# otterley_A_v1_1.net
KiCad netlist of a schematic drawn in EAGLE
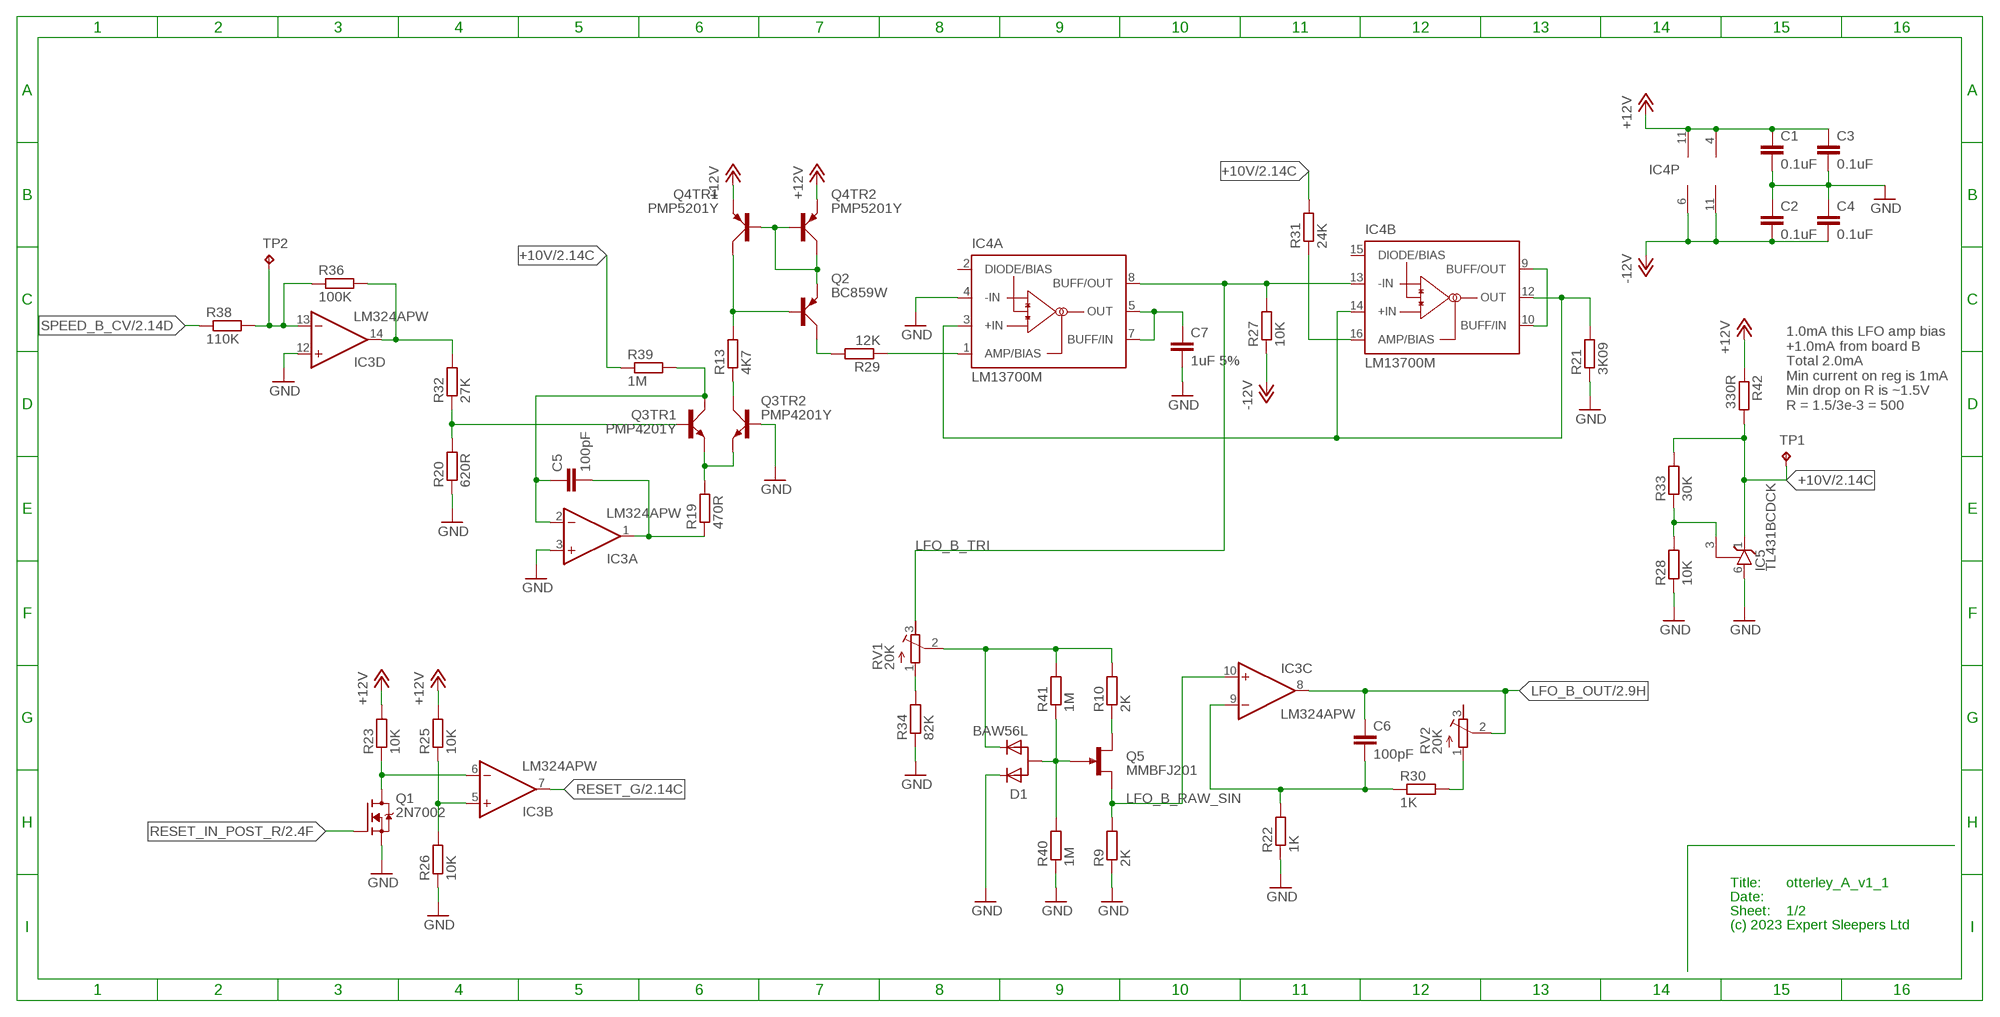
[diagram p0: schematic, sheet 1]
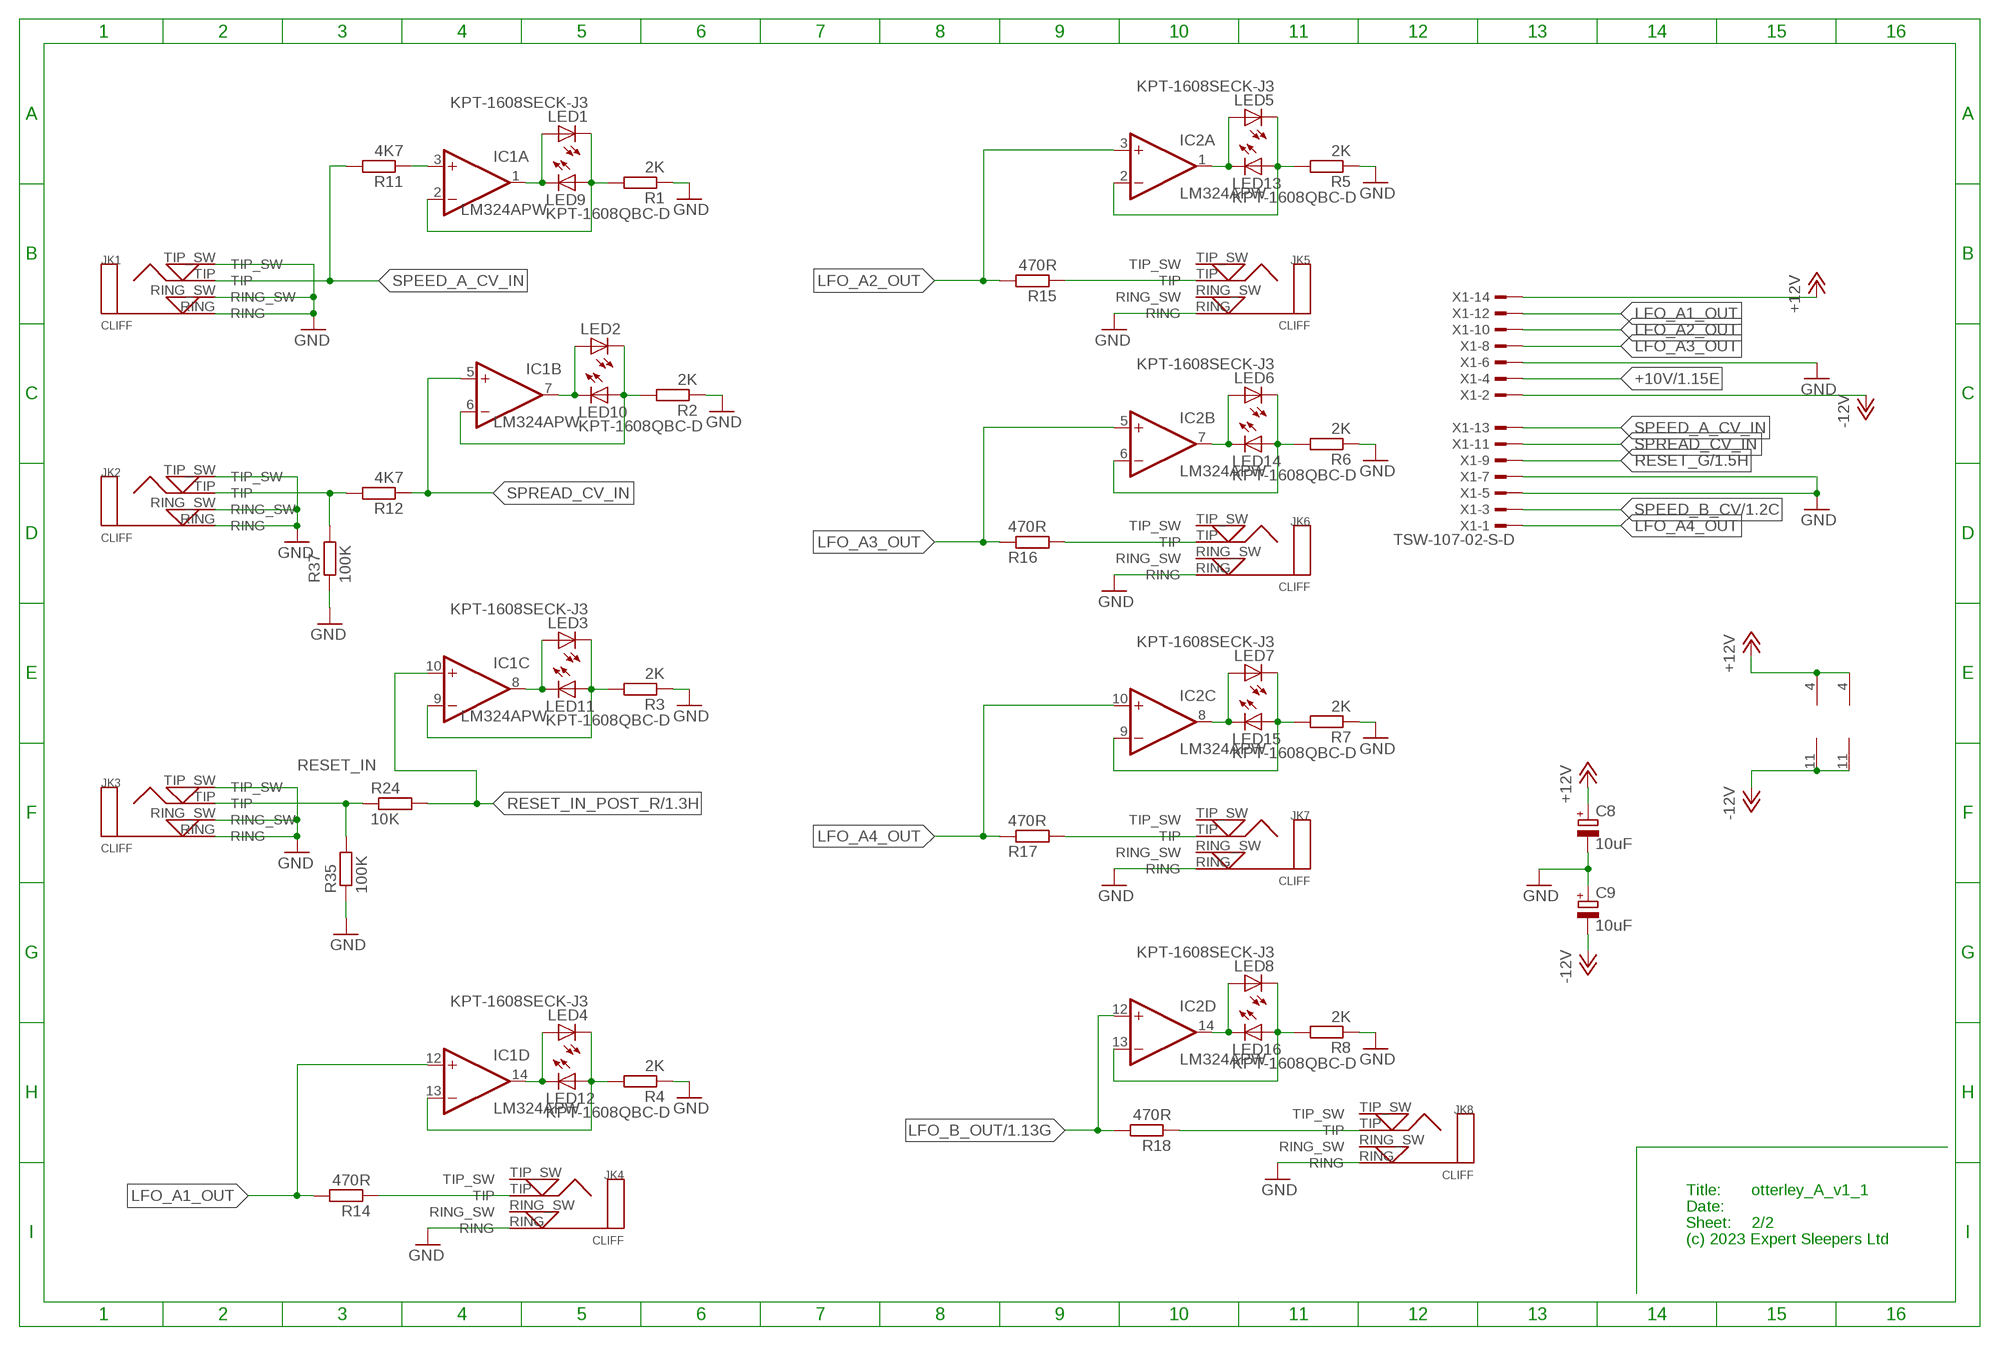
[diagram p1: schematic, sheet 2]

(export (version "E")
  (design (tool "Eeschema 10.0.6"))
  (components
    (comp (ref "C8")
      (value "10uF")
      (footprint "eagle-import:UD-4X5,8_NICHICON")
      (libsource (lib "eagle-import") (part "CPOL-EUUD-4X5,8"))
    )
    (comp (ref "C9")
      (value "10uF")
      (footprint "eagle-import:UD-4X5,8_NICHICON")
      (libsource (lib "eagle-import") (part "CPOL-EUUD-4X5,8"))
    )
    (comp (ref "IC1")
      (value "LM324APW")
      (footprint "eagle-import:PW_R-PDSO-G14")
      (libsource (lib "eagle-import") (part "TL074PW"))
    )
    (comp (ref "IC2")
      (value "LM324APW")
      (footprint "eagle-import:PW_R-PDSO-G14")
      (libsource (lib "eagle-import") (part "TL074PW"))
    )
    (comp (ref "JK1")
      (value "CLIFF")
      (footprint "eagle-import:CLIFF3.5MMPCB")
      (libsource (lib "eagle-import") (part "CLIFF3.5MM_PCB_SW_JK"))
    )
    (comp (ref "JK2")
      (value "CLIFF")
      (footprint "eagle-import:CLIFF3.5MMPCB")
      (libsource (lib "eagle-import") (part "CLIFF3.5MM_PCB_SW_JK"))
    )
    (comp (ref "JK3")
      (value "CLIFF")
      (footprint "eagle-import:CLIFF3.5MMPCB")
      (libsource (lib "eagle-import") (part "CLIFF3.5MM_PCB_SW_JK"))
    )
    (comp (ref "JK4")
      (value "CLIFF")
      (footprint "eagle-import:CLIFF3.5MMPCB")
      (libsource (lib "eagle-import") (part "CLIFF3.5MM_PCB_SW_JK"))
    )
    (comp (ref "JK5")
      (value "CLIFF")
      (footprint "eagle-import:CLIFF3.5MMPCB")
      (libsource (lib "eagle-import") (part "CLIFF3.5MM_PCB_SW_JK"))
    )
    (comp (ref "JK6")
      (value "CLIFF")
      (footprint "eagle-import:CLIFF3.5MMPCB")
      (libsource (lib "eagle-import") (part "CLIFF3.5MM_PCB_SW_JK"))
    )
    (comp (ref "JK7")
      (value "CLIFF")
      (footprint "eagle-import:CLIFF3.5MMPCB")
      (libsource (lib "eagle-import") (part "CLIFF3.5MM_PCB_SW_JK"))
    )
    (comp (ref "JK8")
      (value "CLIFF")
      (footprint "eagle-import:CLIFF3.5MMPCB")
      (libsource (lib "eagle-import") (part "CLIFF3.5MM_PCB_SW_JK"))
    )
    (comp (ref "LED1")
      (value "KPT-1608SECK-J3")
      (footprint "eagle-import:CHIPLED_0603_LEFT")
      (libsource (lib "eagle-import") (part "KPT-1608SECK-J3"))
    )
    (comp (ref "LED2")
      (value "KPT-1608SECK-J3")
      (footprint "eagle-import:CHIPLED_0603_LEFT")
      (libsource (lib "eagle-import") (part "KPT-1608SECK-J3"))
    )
    (comp (ref "LED3")
      (value "KPT-1608SECK-J3")
      (footprint "eagle-import:CHIPLED_0603_LEFT")
      (libsource (lib "eagle-import") (part "KPT-1608SECK-J3"))
    )
    (comp (ref "LED4")
      (value "KPT-1608SECK-J3")
      (footprint "eagle-import:CHIPLED_0603_LEFT")
      (libsource (lib "eagle-import") (part "KPT-1608SECK-J3"))
    )
    (comp (ref "LED5")
      (value "KPT-1608SECK-J3")
      (footprint "eagle-import:CHIPLED_0603_LEFT")
      (libsource (lib "eagle-import") (part "KPT-1608SECK-J3"))
    )
    (comp (ref "LED6")
      (value "KPT-1608SECK-J3")
      (footprint "eagle-import:CHIPLED_0603_LEFT")
      (libsource (lib "eagle-import") (part "KPT-1608SECK-J3"))
    )
    (comp (ref "LED7")
      (value "KPT-1608SECK-J3")
      (footprint "eagle-import:CHIPLED_0603_LEFT")
      (libsource (lib "eagle-import") (part "KPT-1608SECK-J3"))
    )
    (comp (ref "LED8")
      (value "KPT-1608SECK-J3")
      (footprint "eagle-import:CHIPLED_0603_LEFT")
      (libsource (lib "eagle-import") (part "KPT-1608SECK-J3"))
    )
    (comp (ref "LED9")
      (value "KPT-1608QBC-D")
      (footprint "eagle-import:CHIPLED_0603_RIGHT")
      (libsource (lib "eagle-import") (part "KPT-1608QBC-D"))
    )
    (comp (ref "LED10")
      (value "KPT-1608QBC-D")
      (footprint "eagle-import:CHIPLED_0603_RIGHT")
      (libsource (lib "eagle-import") (part "KPT-1608QBC-D"))
    )
    (comp (ref "LED11")
      (value "KPT-1608QBC-D")
      (footprint "eagle-import:CHIPLED_0603_RIGHT")
      (libsource (lib "eagle-import") (part "KPT-1608QBC-D"))
    )
    (comp (ref "LED12")
      (value "KPT-1608QBC-D")
      (footprint "eagle-import:CHIPLED_0603_RIGHT")
      (libsource (lib "eagle-import") (part "KPT-1608QBC-D"))
    )
    (comp (ref "LED13")
      (value "KPT-1608QBC-D")
      (footprint "eagle-import:CHIPLED_0603_RIGHT")
      (libsource (lib "eagle-import") (part "KPT-1608QBC-D"))
    )
    (comp (ref "LED14")
      (value "KPT-1608QBC-D")
      (footprint "eagle-import:CHIPLED_0603_RIGHT")
      (libsource (lib "eagle-import") (part "KPT-1608QBC-D"))
    )
    (comp (ref "LED15")
      (value "KPT-1608QBC-D")
      (footprint "eagle-import:CHIPLED_0603_RIGHT")
      (libsource (lib "eagle-import") (part "KPT-1608QBC-D"))
    )
    (comp (ref "LED16")
      (value "KPT-1608QBC-D")
      (footprint "eagle-import:CHIPLED_0603_RIGHT")
      (libsource (lib "eagle-import") (part "KPT-1608QBC-D"))
    )
    (comp (ref "R1")
      (value "2K")
      (footprint "eagle-import:R1206")
      (libsource (lib "eagle-import") (part "R-EU_R1206"))
    )
    (comp (ref "R2")
      (value "2K")
      (footprint "eagle-import:R1206")
      (libsource (lib "eagle-import") (part "R-EU_R1206"))
    )
    (comp (ref "R3")
      (value "2K")
      (footprint "eagle-import:R1206")
      (libsource (lib "eagle-import") (part "R-EU_R1206"))
    )
    (comp (ref "R4")
      (value "2K")
      (footprint "eagle-import:R1206")
      (libsource (lib "eagle-import") (part "R-EU_R1206"))
    )
    (comp (ref "R5")
      (value "2K")
      (footprint "eagle-import:R1206")
      (libsource (lib "eagle-import") (part "R-EU_R1206"))
    )
    (comp (ref "R6")
      (value "2K")
      (footprint "eagle-import:R1206")
      (libsource (lib "eagle-import") (part "R-EU_R1206"))
    )
    (comp (ref "R7")
      (value "2K")
      (footprint "eagle-import:R1206")
      (libsource (lib "eagle-import") (part "R-EU_R1206"))
    )
    (comp (ref "R8")
      (value "2K")
      (footprint "eagle-import:R1206")
      (libsource (lib "eagle-import") (part "R-EU_R1206"))
    )
    (comp (ref "R11")
      (value "4K7")
      (footprint "eagle-import:R1206")
      (libsource (lib "eagle-import") (part "R-EU_R1206"))
    )
    (comp (ref "R12")
      (value "4K7")
      (footprint "eagle-import:R1206")
      (libsource (lib "eagle-import") (part "R-EU_R1206"))
    )
    (comp (ref "R14")
      (value "470R")
      (footprint "eagle-import:R1206")
      (libsource (lib "eagle-import") (part "R-EU_R1206"))
    )
    (comp (ref "R15")
      (value "470R")
      (footprint "eagle-import:R1206")
      (libsource (lib "eagle-import") (part "R-EU_R1206"))
    )
    (comp (ref "R16")
      (value "470R")
      (footprint "eagle-import:R1206")
      (libsource (lib "eagle-import") (part "R-EU_R1206"))
    )
    (comp (ref "R17")
      (value "470R")
      (footprint "eagle-import:R1206")
      (libsource (lib "eagle-import") (part "R-EU_R1206"))
    )
    (comp (ref "R18")
      (value "470R")
      (footprint "eagle-import:R1206")
      (libsource (lib "eagle-import") (part "R-EU_R1206"))
    )
    (comp (ref "R24")
      (value "10K")
      (footprint "eagle-import:R0603")
      (libsource (lib "eagle-import") (part "R-EU_R0603"))
    )
    (comp (ref "R35")
      (value "100K")
      (footprint "eagle-import:R0603")
      (libsource (lib "eagle-import") (part "R-EU_R0603"))
    )
    (comp (ref "R37")
      (value "100K")
      (footprint "eagle-import:R0603")
      (libsource (lib "eagle-import") (part "R-EU_R0603"))
    )
    (comp (ref "X1")
      (value "TSW-107-02-S-D")
      (footprint "eagle-import:TSW-107-02-S-D")
      (libsource (lib "eagle-import") (part "TSW-107-02-S-D"))
    )
    (comp (ref "C1")
      (value "0.1uF")
      (footprint "eagle-import:C0402")
      (libsource (lib "eagle-import") (part "C-EUC0402"))
    )
    (comp (ref "C2")
      (value "0.1uF")
      (footprint "eagle-import:C0402")
      (libsource (lib "eagle-import") (part "C-EUC0402"))
    )
    (comp (ref "C3")
      (value "0.1uF")
      (footprint "eagle-import:C0402")
      (libsource (lib "eagle-import") (part "C-EUC0402"))
    )
    (comp (ref "C4")
      (value "0.1uF")
      (footprint "eagle-import:C0402")
      (libsource (lib "eagle-import") (part "C-EUC0402"))
    )
    (comp (ref "C5")
      (value "100pF")
      (footprint "eagle-import:C0603")
      (libsource (lib "eagle-import") (part "C-EUC0603"))
    )
    (comp (ref "C6")
      (value "100pF")
      (footprint "eagle-import:C0603")
      (libsource (lib "eagle-import") (part "C-EUC0603"))
    )
    (comp (ref "C7")
      (value "1uF 5%")
      (footprint "eagle-import:C0805")
      (libsource (lib "eagle-import") (part "C-EUC0805"))
    )
    (comp (ref "D1")
      (value "BAW56L")
      (footprint "eagle-import:SOT-23")
      (libsource (lib "eagle-import") (part "BAW56L"))
    )
    (comp (ref "IC3")
      (value "LM324APW")
      (footprint "eagle-import:PW_R-PDSO-G14")
      (libsource (lib "eagle-import") (part "TL074PW"))
    )
    (comp (ref "IC4")
      (value "LM13700M")
      (footprint "eagle-import:SO16")
      (libsource (lib "eagle-import") (part "LM13700M"))
    )
    (comp (ref "IC5")
      (value "TL431BCDCK")
      (footprint "eagle-import:DCK_SC-70")
      (libsource (lib "eagle-import") (part "TL431DCKBC"))
    )
    (comp (ref "Q1")
      (value "2N7002")
      (footprint "eagle-import:SOT23")
      (libsource (lib "eagle-import") (part "2N7002"))
    )
    (comp (ref "Q2")
      (value "BC859W")
      (footprint "eagle-import:SOT323")
      (libsource (lib "eagle-import") (part "BC859W"))
    )
    (comp (ref "Q3")
      (value "PMP4201Y")
      (footprint "eagle-import:SOT65P210X110-6N")
      (fields
        (field (name "ARROW_PART_NUMBER") "PMP4201Y,135")
        (field (name "MOUSER_PART_NUMBER") "771-PMP4201Y135")
      )
      (libsource (lib "eagle-import") (part "PMP4201Y"))
    )
    (comp (ref "Q4")
      (value "PMP5201Y")
      (footprint "eagle-import:SOT65P210X110-6N")
      (fields
        (field (name "ARROW_PART_NUMBER") "PMP5201Y,135")
        (field (name "MOUSER_PART_NUMBER") "771-PMP5201Y135")
      )
      (libsource (lib "eagle-import") (part "PMP5201Y"))
    )
    (comp (ref "Q5")
      (value "MMBFJ201")
      (footprint "eagle-import:SOT23")
      (libsource (lib "eagle-import") (part "MMBFJ3"))
    )
    (comp (ref "R9")
      (value "2K")
      (footprint "eagle-import:R1206")
      (libsource (lib "eagle-import") (part "R-EU_R1206"))
    )
    (comp (ref "R10")
      (value "2K")
      (footprint "eagle-import:R1206")
      (libsource (lib "eagle-import") (part "R-EU_R1206"))
    )
    (comp (ref "R13")
      (value "4K7")
      (footprint "eagle-import:R1206")
      (libsource (lib "eagle-import") (part "R-EU_R1206"))
    )
    (comp (ref "R19")
      (value "470R")
      (footprint "eagle-import:R1206")
      (libsource (lib "eagle-import") (part "R-EU_R1206"))
    )
    (comp (ref "R20")
      (value "620R")
      (footprint "eagle-import:R0603")
      (libsource (lib "eagle-import") (part "R-EU_R0603"))
    )
    (comp (ref "R21")
      (value "3K09")
      (footprint "eagle-import:R0603")
      (libsource (lib "eagle-import") (part "R-EU_R0603"))
    )
    (comp (ref "R22")
      (value "1K")
      (footprint "eagle-import:R0603")
      (libsource (lib "eagle-import") (part "R-EU_R0603"))
    )
    (comp (ref "R23")
      (value "10K")
      (footprint "eagle-import:R0603")
      (libsource (lib "eagle-import") (part "R-EU_R0603"))
    )
    (comp (ref "R25")
      (value "10K")
      (footprint "eagle-import:R0603")
      (libsource (lib "eagle-import") (part "R-EU_R0603"))
    )
    (comp (ref "R26")
      (value "10K")
      (footprint "eagle-import:R0603")
      (libsource (lib "eagle-import") (part "R-EU_R0603"))
    )
    (comp (ref "R27")
      (value "10K")
      (footprint "eagle-import:R0603")
      (libsource (lib "eagle-import") (part "R-EU_R0603"))
    )
    (comp (ref "R28")
      (value "10K")
      (footprint "eagle-import:R0603")
      (libsource (lib "eagle-import") (part "R-EU_R0603"))
    )
    (comp (ref "R29")
      (value "12K")
      (footprint "eagle-import:R0603")
      (libsource (lib "eagle-import") (part "R-EU_R0603"))
    )
    (comp (ref "R30")
      (value "1K")
      (footprint "eagle-import:R0603")
      (libsource (lib "eagle-import") (part "R-EU_R0603"))
    )
    (comp (ref "R31")
      (value "24K")
      (footprint "eagle-import:R0603")
      (libsource (lib "eagle-import") (part "R-EU_R0603"))
    )
    (comp (ref "R32")
      (value "27K")
      (footprint "eagle-import:R0603")
      (libsource (lib "eagle-import") (part "R-EU_R0603"))
    )
    (comp (ref "R33")
      (value "30K")
      (footprint "eagle-import:R0603")
      (libsource (lib "eagle-import") (part "R-EU_R0603"))
    )
    (comp (ref "R34")
      (value "82K")
      (footprint "eagle-import:R0603")
      (libsource (lib "eagle-import") (part "R-EU_R0603"))
    )
    (comp (ref "R36")
      (value "100K")
      (footprint "eagle-import:R0603")
      (libsource (lib "eagle-import") (part "R-EU_R0603"))
    )
    (comp (ref "R38")
      (value "110K")
      (footprint "eagle-import:R0603")
      (libsource (lib "eagle-import") (part "R-EU_R0603"))
    )
    (comp (ref "R39")
      (value "1M")
      (footprint "eagle-import:R0603")
      (libsource (lib "eagle-import") (part "R-EU_R0603"))
    )
    (comp (ref "R40")
      (value "1M")
      (footprint "eagle-import:R0603")
      (libsource (lib "eagle-import") (part "R-EU_R0603"))
    )
    (comp (ref "R41")
      (value "1M")
      (footprint "eagle-import:R0603")
      (libsource (lib "eagle-import") (part "R-EU_R0603"))
    )
    (comp (ref "R42")
      (value "330R")
      (footprint "eagle-import:R1206")
      (libsource (lib "eagle-import") (part "R-EU_R1206"))
    )
    (comp (ref "RV1")
      (value "20K")
      (footprint "eagle-import:3306_W")
      (libsource (lib "eagle-import") (part "3306W"))
    )
    (comp (ref "RV2")
      (value "20K")
      (footprint "eagle-import:3306_W")
      (libsource (lib "eagle-import") (part "3306W"))
    )
    (comp (ref "TP1")
      (value "RA2")
      (footprint "eagle-import:P1-13")
      (libsource (lib "eagle-import") (part "TPPAD1-13"))
    )
    (comp (ref "TP2")
      (value "RA2")
      (footprint "eagle-import:P1-13")
      (libsource (lib "eagle-import") (part "TPPAD1-13"))
    )
  )
  (nets
    (net (code "1") (name "+10V") (class "Default")
      (node (ref "IC5") (pin "1") (pinfunction "C_1") (pintype "passive"))
      (node (ref "R31") (pin "2") (pinfunction "2_2") (pintype "passive"))
      (node (ref "R33") (pin "2") (pinfunction "2_2") (pintype "passive"))
      (node (ref "R39") (pin "1") (pinfunction "1_1") (pintype "passive"))
      (node (ref "R42") (pin "2") (pinfunction "2_2") (pintype "passive"))
      (node (ref "TP1") (pin "TP") (pinfunction "TP_TP") (pintype "input"))
      (node (ref "X1") (pin "4") (pinfunction "1_4") (pintype "passive"))
    )
    (net (code "2") (name "+12V") (class "Default")
      (node (ref "C1") (pin "1") (pinfunction "1_1") (pintype "passive"))
      (node (ref "C3") (pin "1") (pinfunction "1_1") (pintype "passive"))
      (node (ref "C8") (pin "+") (pinfunction "+_+") (pintype "passive"))
      (node (ref "IC1") (pin "4") (pinfunction "V+_4") (pintype "power_in"))
      (node (ref "IC2") (pin "4") (pinfunction "V+_4") (pintype "power_in"))
      (node (ref "IC3") (pin "4") (pinfunction "V+_4") (pintype "power_in"))
      (node (ref "IC4") (pin "11") (pinfunction "V+_11") (pintype "power_in"))
      (node (ref "Q4") (pin "4") (pinfunction "E_4") (pintype "passive"))
      (node (ref "Q4") (pin "5") (pinfunction "E_5") (pintype "passive"))
      (node (ref "R23") (pin "2") (pinfunction "2_2") (pintype "passive"))
      (node (ref "R25") (pin "2") (pinfunction "2_2") (pintype "passive"))
      (node (ref "R42") (pin "1") (pinfunction "1_1") (pintype "passive"))
      (node (ref "X1") (pin "14") (pinfunction "1_14") (pintype "passive"))
    )
    (net (code "3") (name "-12V") (class "Default")
      (node (ref "C2") (pin "2") (pinfunction "2_2") (pintype "passive"))
      (node (ref "C4") (pin "2") (pinfunction "2_2") (pintype "passive"))
      (node (ref "C9") (pin "-") (pinfunction "-_-") (pintype "passive"))
      (node (ref "IC1") (pin "11") (pinfunction "V-_11") (pintype "power_in"))
      (node (ref "IC2") (pin "11") (pinfunction "V-_11") (pintype "power_in"))
      (node (ref "IC3") (pin "11") (pinfunction "V-_11") (pintype "power_in"))
      (node (ref "IC4") (pin "6") (pinfunction "V-_6") (pintype "power_in"))
      (node (ref "R27") (pin "1") (pinfunction "1_1") (pintype "passive"))
      (node (ref "X1") (pin "2") (pinfunction "1_2") (pintype "passive"))
    )
    (net (code "4") (name "GND") (class "Default")
      (node (ref "C1") (pin "2") (pinfunction "2_2") (pintype "passive"))
      (node (ref "C2") (pin "1") (pinfunction "1_1") (pintype "passive"))
      (node (ref "C3") (pin "2") (pinfunction "2_2") (pintype "passive"))
      (node (ref "C4") (pin "1") (pinfunction "1_1") (pintype "passive"))
      (node (ref "C7") (pin "2") (pinfunction "2_2") (pintype "passive"))
      (node (ref "C8") (pin "-") (pinfunction "-_-") (pintype "passive"))
      (node (ref "C9") (pin "+") (pinfunction "+_+") (pintype "passive"))
      (node (ref "D1") (pin "1") (pinfunction "C1_1") (pintype "passive"))
      (node (ref "IC3") (pin "12") (pinfunction "+IN_12") (pintype "input"))
      (node (ref "IC3") (pin "3") (pinfunction "+IN_3") (pintype "input"))
      (node (ref "IC4") (pin "4") (pinfunction "-IN_4") (pintype "input"))
      (node (ref "IC5") (pin "6") (pinfunction "A_6") (pintype "passive"))
      (node (ref "JK1") (pin "RING") (pinfunction "RING_RING") (pintype "bidirectional"))
      (node (ref "JK1") (pin "RING_SW") (pinfunction "RING_SW_RING_SW") (pintype "bidirectional"))
      (node (ref "JK1") (pin "TIP_SW") (pinfunction "TIP_SW_TIP_SW") (pintype "bidirectional"))
      (node (ref "JK2") (pin "RING") (pinfunction "RING_RING") (pintype "bidirectional"))
      (node (ref "JK2") (pin "RING_SW") (pinfunction "RING_SW_RING_SW") (pintype "bidirectional"))
      (node (ref "JK2") (pin "TIP_SW") (pinfunction "TIP_SW_TIP_SW") (pintype "bidirectional"))
      (node (ref "JK3") (pin "RING") (pinfunction "RING_RING") (pintype "bidirectional"))
      (node (ref "JK3") (pin "RING_SW") (pinfunction "RING_SW_RING_SW") (pintype "bidirectional"))
      (node (ref "JK3") (pin "TIP_SW") (pinfunction "TIP_SW_TIP_SW") (pintype "bidirectional"))
      (node (ref "JK4") (pin "RING") (pinfunction "RING_RING") (pintype "bidirectional"))
      (node (ref "JK5") (pin "RING") (pinfunction "RING_RING") (pintype "bidirectional"))
      (node (ref "JK6") (pin "RING") (pinfunction "RING_RING") (pintype "bidirectional"))
      (node (ref "JK7") (pin "RING") (pinfunction "RING_RING") (pintype "bidirectional"))
      (node (ref "JK8") (pin "RING") (pinfunction "RING_RING") (pintype "bidirectional"))
      (node (ref "Q1") (pin "2") (pinfunction "S_2") (pintype "passive"))
      (node (ref "Q3") (pin "2") (pinfunction "B_2") (pintype "passive"))
      (node (ref "R1") (pin "1") (pinfunction "1_1") (pintype "passive"))
      (node (ref "R2") (pin "1") (pinfunction "1_1") (pintype "passive"))
      (node (ref "R20") (pin "1") (pinfunction "1_1") (pintype "passive"))
      (node (ref "R21") (pin "1") (pinfunction "1_1") (pintype "passive"))
      (node (ref "R22") (pin "1") (pinfunction "1_1") (pintype "passive"))
      (node (ref "R26") (pin "1") (pinfunction "1_1") (pintype "passive"))
      (node (ref "R28") (pin "1") (pinfunction "1_1") (pintype "passive"))
      (node (ref "R3") (pin "1") (pinfunction "1_1") (pintype "passive"))
      (node (ref "R34") (pin "1") (pinfunction "1_1") (pintype "passive"))
      (node (ref "R35") (pin "1") (pinfunction "1_1") (pintype "passive"))
      (node (ref "R37") (pin "1") (pinfunction "1_1") (pintype "passive"))
      (node (ref "R4") (pin "1") (pinfunction "1_1") (pintype "passive"))
      (node (ref "R40") (pin "1") (pinfunction "1_1") (pintype "passive"))
      (node (ref "R5") (pin "1") (pinfunction "1_1") (pintype "passive"))
      (node (ref "R6") (pin "1") (pinfunction "1_1") (pintype "passive"))
      (node (ref "R7") (pin "1") (pinfunction "1_1") (pintype "passive"))
      (node (ref "R8") (pin "1") (pinfunction "1_1") (pintype "passive"))
      (node (ref "R9") (pin "1") (pinfunction "1_1") (pintype "passive"))
      (node (ref "X1") (pin "5") (pinfunction "1_5") (pintype "passive"))
      (node (ref "X1") (pin "6") (pinfunction "1_6") (pintype "passive"))
      (node (ref "X1") (pin "7") (pinfunction "1_7") (pintype "passive"))
    )
    (net (code "5") (name "LFO_A1_OUT") (class "Default")
      (node (ref "IC1") (pin "12") (pinfunction "+IN_12") (pintype "input"))
      (node (ref "R14") (pin "2") (pinfunction "2_2") (pintype "passive"))
      (node (ref "X1") (pin "12") (pinfunction "1_12") (pintype "passive"))
    )
    (net (code "6") (name "LFO_A2_OUT") (class "Default")
      (node (ref "IC2") (pin "3") (pinfunction "+IN_3") (pintype "input"))
      (node (ref "R15") (pin "2") (pinfunction "2_2") (pintype "passive"))
      (node (ref "X1") (pin "10") (pinfunction "1_10") (pintype "passive"))
    )
    (net (code "7") (name "LFO_A3_OUT") (class "Default")
      (node (ref "IC2") (pin "5") (pinfunction "+IN_5") (pintype "input"))
      (node (ref "R16") (pin "1") (pinfunction "1_1") (pintype "passive"))
      (node (ref "X1") (pin "8") (pinfunction "1_8") (pintype "passive"))
    )
    (net (code "8") (name "LFO_A4_OUT") (class "Default")
      (node (ref "IC2") (pin "10") (pinfunction "+IN_10") (pintype "input"))
      (node (ref "R17") (pin "1") (pinfunction "1_1") (pintype "passive"))
      (node (ref "X1") (pin "1") (pinfunction "1_1") (pintype "passive"))
    )
    (net (code "9") (name "LFO_B_OUT") (class "Default")
      (node (ref "C6") (pin "1") (pinfunction "1_1") (pintype "passive"))
      (node (ref "IC2") (pin "12") (pinfunction "+IN_12") (pintype "input"))
      (node (ref "IC3") (pin "8") (pinfunction "OUT_8") (pintype "output"))
      (node (ref "R18") (pin "2") (pinfunction "2_2") (pintype "passive"))
      (node (ref "RV2") (pin "2") (pinfunction "S_2") (pintype "passive"))
    )
    (net (code "10") (name "LFO_B_RAW_SIN") (class "Default")
      (node (ref "IC3") (pin "10") (pinfunction "+IN_10") (pintype "input"))
      (node (ref "Q5") (pin "2") (pinfunction "S_2") (pintype "passive"))
      (node (ref "R9") (pin "2") (pinfunction "2_2") (pintype "passive"))
    )
    (net (code "11") (name "LFO_B_TRI") (class "Default")
      (node (ref "IC4") (pin "13") (pinfunction "-IN_13") (pintype "input"))
      (node (ref "IC4") (pin "8") (pinfunction "BUFF/OUT_8") (pintype "output"))
      (node (ref "R27") (pin "2") (pinfunction "2_2") (pintype "passive"))
      (node (ref "RV1") (pin "3") (pinfunction "E_3") (pintype "passive"))
    )
    (net (code "12") (name "Net-(D1-A)") (class "Default")
      (node (ref "D1") (pin "3") (pinfunction "A_3") (pintype "passive"))
      (node (ref "Q5") (pin "3") (pinfunction "G_3") (pintype "passive"))
      (node (ref "R40") (pin "2") (pinfunction "2_2") (pintype "passive"))
      (node (ref "R41") (pin "1") (pinfunction "1_1") (pintype "passive"))
    )
    (net (code "13") (name "Net-(D1-C2)") (class "Default")
      (node (ref "D1") (pin "2") (pinfunction "C2_2") (pintype "passive"))
      (node (ref "R10") (pin "2") (pinfunction "2_2") (pintype "passive"))
      (node (ref "R41") (pin "2") (pinfunction "2_2") (pintype "passive"))
      (node (ref "RV1") (pin "2") (pinfunction "S_2") (pintype "passive"))
    )
    (net (code "14") (name "Net-(IC1A-+IN)") (class "Default")
      (node (ref "IC1") (pin "3") (pinfunction "+IN_3") (pintype "input"))
      (node (ref "R11") (pin "1") (pinfunction "1_1") (pintype "passive"))
    )
    (net (code "15") (name "Net-(IC1A--IN)") (class "Default")
      (node (ref "IC1") (pin "2") (pinfunction "-IN_2") (pintype "input"))
      (node (ref "LED1") (pin "1") (pinfunction "C_1") (pintype "passive"))
      (node (ref "LED9") (pin "1") (pinfunction "A_1") (pintype "passive"))
      (node (ref "R1") (pin "2") (pinfunction "2_2") (pintype "passive"))
    )
    (net (code "16") (name "Net-(IC1A-OUT)") (class "Default")
      (node (ref "IC1") (pin "1") (pinfunction "OUT_1") (pintype "output"))
      (node (ref "LED1") (pin "2") (pinfunction "A_2") (pintype "passive"))
      (node (ref "LED9") (pin "2") (pinfunction "C_2") (pintype "passive"))
    )
    (net (code "17") (name "Net-(IC1B--IN)") (class "Default")
      (node (ref "IC1") (pin "6") (pinfunction "-IN_6") (pintype "input"))
      (node (ref "LED10") (pin "1") (pinfunction "A_1") (pintype "passive"))
      (node (ref "LED2") (pin "1") (pinfunction "C_1") (pintype "passive"))
      (node (ref "R2") (pin "2") (pinfunction "2_2") (pintype "passive"))
    )
    (net (code "18") (name "Net-(IC1B-OUT)") (class "Default")
      (node (ref "IC1") (pin "7") (pinfunction "OUT_7") (pintype "output"))
      (node (ref "LED10") (pin "2") (pinfunction "C_2") (pintype "passive"))
      (node (ref "LED2") (pin "2") (pinfunction "A_2") (pintype "passive"))
    )
    (net (code "19") (name "Net-(IC1C--IN)") (class "Default")
      (node (ref "IC1") (pin "9") (pinfunction "-IN_9") (pintype "input"))
      (node (ref "LED11") (pin "1") (pinfunction "A_1") (pintype "passive"))
      (node (ref "LED3") (pin "1") (pinfunction "C_1") (pintype "passive"))
      (node (ref "R3") (pin "2") (pinfunction "2_2") (pintype "passive"))
    )
    (net (code "20") (name "Net-(IC1C-OUT)") (class "Default")
      (node (ref "IC1") (pin "8") (pinfunction "OUT_8") (pintype "output"))
      (node (ref "LED11") (pin "2") (pinfunction "C_2") (pintype "passive"))
      (node (ref "LED3") (pin "2") (pinfunction "A_2") (pintype "passive"))
    )
    (net (code "21") (name "Net-(IC1D--IN)") (class "Default")
      (node (ref "IC1") (pin "13") (pinfunction "-IN_13") (pintype "input"))
      (node (ref "LED12") (pin "1") (pinfunction "A_1") (pintype "passive"))
      (node (ref "LED4") (pin "1") (pinfunction "C_1") (pintype "passive"))
      (node (ref "R4") (pin "2") (pinfunction "2_2") (pintype "passive"))
    )
    (net (code "22") (name "Net-(IC1D-OUT)") (class "Default")
      (node (ref "IC1") (pin "14") (pinfunction "OUT_14") (pintype "output"))
      (node (ref "LED12") (pin "2") (pinfunction "C_2") (pintype "passive"))
      (node (ref "LED4") (pin "2") (pinfunction "A_2") (pintype "passive"))
    )
    (net (code "23") (name "Net-(IC2A--IN)") (class "Default")
      (node (ref "IC2") (pin "2") (pinfunction "-IN_2") (pintype "input"))
      (node (ref "LED13") (pin "1") (pinfunction "A_1") (pintype "passive"))
      (node (ref "LED5") (pin "1") (pinfunction "C_1") (pintype "passive"))
      (node (ref "R5") (pin "2") (pinfunction "2_2") (pintype "passive"))
    )
    (net (code "24") (name "Net-(IC2A-OUT)") (class "Default")
      (node (ref "IC2") (pin "1") (pinfunction "OUT_1") (pintype "output"))
      (node (ref "LED13") (pin "2") (pinfunction "C_2") (pintype "passive"))
      (node (ref "LED5") (pin "2") (pinfunction "A_2") (pintype "passive"))
    )
    (net (code "25") (name "Net-(IC2B--IN)") (class "Default")
      (node (ref "IC2") (pin "6") (pinfunction "-IN_6") (pintype "input"))
      (node (ref "LED14") (pin "1") (pinfunction "A_1") (pintype "passive"))
      (node (ref "LED6") (pin "1") (pinfunction "C_1") (pintype "passive"))
      (node (ref "R6") (pin "2") (pinfunction "2_2") (pintype "passive"))
    )
    (net (code "26") (name "Net-(IC2B-OUT)") (class "Default")
      (node (ref "IC2") (pin "7") (pinfunction "OUT_7") (pintype "output"))
      (node (ref "LED14") (pin "2") (pinfunction "C_2") (pintype "passive"))
      (node (ref "LED6") (pin "2") (pinfunction "A_2") (pintype "passive"))
    )
    (net (code "27") (name "Net-(IC2C--IN)") (class "Default")
      (node (ref "IC2") (pin "9") (pinfunction "-IN_9") (pintype "input"))
      (node (ref "LED15") (pin "1") (pinfunction "A_1") (pintype "passive"))
      (node (ref "LED7") (pin "1") (pinfunction "C_1") (pintype "passive"))
      (node (ref "R7") (pin "2") (pinfunction "2_2") (pintype "passive"))
    )
    (net (code "28") (name "Net-(IC2C-OUT)") (class "Default")
      (node (ref "IC2") (pin "8") (pinfunction "OUT_8") (pintype "output"))
      (node (ref "LED15") (pin "2") (pinfunction "C_2") (pintype "passive"))
      (node (ref "LED7") (pin "2") (pinfunction "A_2") (pintype "passive"))
    )
    (net (code "29") (name "Net-(IC2D--IN)") (class "Default")
      (node (ref "IC2") (pin "13") (pinfunction "-IN_13") (pintype "input"))
      (node (ref "LED16") (pin "1") (pinfunction "A_1") (pintype "passive"))
      (node (ref "LED8") (pin "1") (pinfunction "C_1") (pintype "passive"))
      (node (ref "R8") (pin "2") (pinfunction "2_2") (pintype "passive"))
    )
    (net (code "30") (name "Net-(IC2D-OUT)") (class "Default")
      (node (ref "IC2") (pin "14") (pinfunction "OUT_14") (pintype "output"))
      (node (ref "LED16") (pin "2") (pinfunction "C_2") (pintype "passive"))
      (node (ref "LED8") (pin "2") (pinfunction "A_2") (pintype "passive"))
    )
    (net (code "31") (name "Net-(IC3A--IN)") (class "Default")
      (node (ref "C5") (pin "1") (pinfunction "1_1") (pintype "passive"))
      (node (ref "IC3") (pin "2") (pinfunction "-IN_2") (pintype "input"))
      (node (ref "Q3") (pin "6") (pinfunction "C_6") (pintype "passive"))
      (node (ref "R39") (pin "2") (pinfunction "2_2") (pintype "passive"))
    )
    (net (code "32") (name "Net-(IC3A-OUT)") (class "Default")
      (node (ref "C5") (pin "2") (pinfunction "2_2") (pintype "passive"))
      (node (ref "IC3") (pin "1") (pinfunction "OUT_1") (pintype "output"))
      (node (ref "R19") (pin "1") (pinfunction "1_1") (pintype "passive"))
    )
    (net (code "33") (name "Net-(IC3B-+IN)") (class "Default")
      (node (ref "IC3") (pin "5") (pinfunction "+IN_5") (pintype "input"))
      (node (ref "R25") (pin "1") (pinfunction "1_1") (pintype "passive"))
      (node (ref "R26") (pin "2") (pinfunction "2_2") (pintype "passive"))
    )
    (net (code "34") (name "Net-(IC3B--IN)") (class "Default")
      (node (ref "IC3") (pin "6") (pinfunction "-IN_6") (pintype "input"))
      (node (ref "Q1") (pin "3") (pinfunction "D_3") (pintype "passive"))
      (node (ref "R23") (pin "1") (pinfunction "1_1") (pintype "passive"))
    )
    (net (code "35") (name "Net-(IC3C--IN)") (class "Default")
      (node (ref "C6") (pin "2") (pinfunction "2_2") (pintype "passive"))
      (node (ref "IC3") (pin "9") (pinfunction "-IN_9") (pintype "input"))
      (node (ref "R22") (pin "2") (pinfunction "2_2") (pintype "passive"))
      (node (ref "R30") (pin "1") (pinfunction "1_1") (pintype "passive"))
    )
    (net (code "36") (name "Net-(IC3D--IN)") (class "Default")
      (node (ref "IC3") (pin "13") (pinfunction "-IN_13") (pintype "input"))
      (node (ref "R36") (pin "1") (pinfunction "1_1") (pintype "passive"))
      (node (ref "R38") (pin "2") (pinfunction "2_2") (pintype "passive"))
      (node (ref "TP2") (pin "TP") (pinfunction "TP_TP") (pintype "input"))
    )
    (net (code "37") (name "Net-(IC3D-OUT)") (class "Default")
      (node (ref "IC3") (pin "14") (pinfunction "OUT_14") (pintype "output"))
      (node (ref "R32") (pin "2") (pinfunction "2_2") (pintype "passive"))
      (node (ref "R36") (pin "2") (pinfunction "2_2") (pintype "passive"))
    )
    (net (code "38") (name "Net-(IC4A-+IN)") (class "Default")
      (node (ref "IC4") (pin "12") (pinfunction "OUT_12") (pintype "output"))
      (node (ref "IC4") (pin "14") (pinfunction "+IN_14") (pintype "input"))
      (node (ref "IC4") (pin "3") (pinfunction "+IN_3") (pintype "input"))
      (node (ref "R21") (pin "2") (pinfunction "2_2") (pintype "passive"))
    )
    (net (code "39") (name "Net-(IC4A-AMP{slash}BIAS)") (class "Default")
      (node (ref "IC4") (pin "1") (pinfunction "AMP/BIAS_1") (pintype "passive"))
      (node (ref "R29") (pin "1") (pinfunction "1_1") (pintype "passive"))
    )
    (net (code "40") (name "Net-(IC4A-BUFF{slash}IN)") (class "Default")
      (node (ref "C7") (pin "1") (pinfunction "1_1") (pintype "passive"))
      (node (ref "IC4") (pin "5") (pinfunction "OUT_5") (pintype "output"))
      (node (ref "IC4") (pin "7") (pinfunction "BUFF/IN_7") (pintype "input"))
    )
    (net (code "41") (name "Net-(IC4B-AMP{slash}BIAS)") (class "Default")
      (node (ref "IC4") (pin "16") (pinfunction "AMP/BIAS_16") (pintype "passive"))
      (node (ref "R31") (pin "1") (pinfunction "1_1") (pintype "passive"))
    )
    (net (code "42") (name "Net-(IC4B-BUFF{slash}IN)") (class "Default")
      (node (ref "IC4") (pin "10") (pinfunction "BUFF/IN_10") (pintype "input"))
      (node (ref "IC4") (pin "9") (pinfunction "BUFF/OUT_9") (pintype "output"))
    )
    (net (code "43") (name "Net-(IC5-R)") (class "Default")
      (node (ref "IC5") (pin "3") (pinfunction "R_3") (pintype "passive"))
      (node (ref "R28") (pin "2") (pinfunction "2_2") (pintype "passive"))
      (node (ref "R33") (pin "1") (pinfunction "1_1") (pintype "passive"))
    )
    (net (code "44") (name "Net-(JK2-PadTIP)") (class "Default")
      (node (ref "JK2") (pin "TIP") (pinfunction "TIP_TIP") (pintype "bidirectional"))
      (node (ref "R12") (pin "2") (pinfunction "2_2") (pintype "passive"))
      (node (ref "R37") (pin "2") (pinfunction "2_2") (pintype "passive"))
    )
    (net (code "45") (name "Net-(JK4-PadTIP)") (class "Default")
      (node (ref "JK4") (pin "TIP") (pinfunction "TIP_TIP") (pintype "bidirectional"))
      (node (ref "R14") (pin "1") (pinfunction "1_1") (pintype "passive"))
    )
    (net (code "46") (name "Net-(JK5-PadTIP)") (class "Default")
      (node (ref "JK5") (pin "TIP") (pinfunction "TIP_TIP") (pintype "bidirectional"))
      (node (ref "R15") (pin "1") (pinfunction "1_1") (pintype "passive"))
    )
    (net (code "47") (name "Net-(JK6-PadTIP)") (class "Default")
      (node (ref "JK6") (pin "TIP") (pinfunction "TIP_TIP") (pintype "bidirectional"))
      (node (ref "R16") (pin "2") (pinfunction "2_2") (pintype "passive"))
    )
    (net (code "48") (name "Net-(JK7-PadTIP)") (class "Default")
      (node (ref "JK7") (pin "TIP") (pinfunction "TIP_TIP") (pintype "bidirectional"))
      (node (ref "R17") (pin "2") (pinfunction "2_2") (pintype "passive"))
    )
    (net (code "49") (name "Net-(JK8-PadTIP)") (class "Default")
      (node (ref "JK8") (pin "TIP") (pinfunction "TIP_TIP") (pintype "bidirectional"))
      (node (ref "R18") (pin "1") (pinfunction "1_1") (pintype "passive"))
    )
    (net (code "50") (name "Net-(Q2-B)") (class "Default")
      (node (ref "Q2") (pin "1") (pinfunction "B_1") (pintype "passive"))
      (node (ref "Q4") (pin "6") (pinfunction "C_6") (pintype "passive"))
      (node (ref "R13") (pin "2") (pinfunction "2_2") (pintype "passive"))
    )
    (net (code "51") (name "Net-(Q2-C)") (class "Default")
      (node (ref "Q2") (pin "3") (pinfunction "C_3") (pintype "passive"))
      (node (ref "R29") (pin "2") (pinfunction "2_2") (pintype "passive"))
    )
    (net (code "52") (name "Net-(Q2-E)") (class "Default")
      (node (ref "Q2") (pin "2") (pinfunction "E_2") (pintype "passive"))
      (node (ref "Q4") (pin "1") (pinfunction "B_1") (pintype "passive"))
      (node (ref "Q4") (pin "2") (pinfunction "B_2") (pintype "passive"))
      (node (ref "Q4") (pin "3") (pinfunction "C_3") (pintype "passive"))
    )
    (net (code "53") (name "Net-(Q3A-B)") (class "Default")
      (node (ref "Q3") (pin "1") (pinfunction "B_1") (pintype "passive"))
      (node (ref "R20") (pin "2") (pinfunction "2_2") (pintype "passive"))
      (node (ref "R32") (pin "1") (pinfunction "1_1") (pintype "passive"))
    )
    (net (code "54") (name "Net-(Q3A-E)") (class "Default")
      (node (ref "Q3") (pin "4") (pinfunction "E_4") (pintype "passive"))
      (node (ref "Q3") (pin "5") (pinfunction "E_5") (pintype "passive"))
      (node (ref "R19") (pin "2") (pinfunction "2_2") (pintype "passive"))
    )
    (net (code "55") (name "Net-(Q3B-C)") (class "Default")
      (node (ref "Q3") (pin "3") (pinfunction "C_3") (pintype "passive"))
      (node (ref "R13") (pin "1") (pinfunction "1_1") (pintype "passive"))
    )
    (net (code "56") (name "Net-(Q5-D)") (class "Default")
      (node (ref "Q5") (pin "1") (pinfunction "D_1") (pintype "passive"))
      (node (ref "R10") (pin "1") (pinfunction "1_1") (pintype "passive"))
    )
    (net (code "57") (name "Net-(RV1-A)") (class "Default")
      (node (ref "R34") (pin "2") (pinfunction "2_2") (pintype "passive"))
      (node (ref "RV1") (pin "1") (pinfunction "A_1") (pintype "passive"))
    )
    (net (code "58") (name "Net-(RV2-A)") (class "Default")
      (node (ref "R30") (pin "2") (pinfunction "2_2") (pintype "passive"))
      (node (ref "RV2") (pin "1") (pinfunction "A_1") (pintype "passive"))
    )
    (net (code "59") (name "RESET_G") (class "Default")
      (node (ref "IC3") (pin "7") (pinfunction "OUT_7") (pintype "output"))
      (node (ref "X1") (pin "9") (pinfunction "1_9") (pintype "passive"))
    )
    (net (code "60") (name "RESET_IN") (class "Default")
      (node (ref "JK3") (pin "TIP") (pinfunction "TIP_TIP") (pintype "bidirectional"))
      (node (ref "R24") (pin "1") (pinfunction "1_1") (pintype "passive"))
      (node (ref "R35") (pin "2") (pinfunction "2_2") (pintype "passive"))
    )
    (net (code "61") (name "RESET_IN_POST_R") (class "Default")
      (node (ref "IC1") (pin "10") (pinfunction "+IN_10") (pintype "input"))
      (node (ref "Q1") (pin "1") (pinfunction "G_1") (pintype "passive"))
      (node (ref "R24") (pin "2") (pinfunction "2_2") (pintype "passive"))
    )
    (net (code "62") (name "SPEED_A_CV_IN") (class "Default")
      (node (ref "JK1") (pin "TIP") (pinfunction "TIP_TIP") (pintype "bidirectional"))
      (node (ref "R11") (pin "2") (pinfunction "2_2") (pintype "passive"))
      (node (ref "X1") (pin "13") (pinfunction "1_13") (pintype "passive"))
    )
    (net (code "63") (name "SPEED_B_CV") (class "Default")
      (node (ref "R38") (pin "1") (pinfunction "1_1") (pintype "passive"))
      (node (ref "X1") (pin "3") (pinfunction "1_3") (pintype "passive"))
    )
    (net (code "64") (name "SPREAD_CV_IN") (class "Default")
      (node (ref "IC1") (pin "5") (pinfunction "+IN_5") (pintype "input"))
      (node (ref "R12") (pin "1") (pinfunction "1_1") (pintype "passive"))
      (node (ref "X1") (pin "11") (pinfunction "1_11") (pintype "passive"))
    )
    (net (code "65") (name "unconnected-(IC4A-DIODE{slash}BIAS-Pad2)") (class "Default")
      (node (ref "IC4") (pin "2") (pinfunction "DIODE/BIAS_2") (pintype "passive"))
    )
    (net (code "66") (name "unconnected-(IC4B-DIODE{slash}BIAS-Pad15)") (class "Default")
      (node (ref "IC4") (pin "15") (pinfunction "DIODE/BIAS_15") (pintype "passive"))
    )
    (net (code "67") (name "unconnected-(JK4-PadRING_SW)") (class "Default")
      (node (ref "JK4") (pin "RING_SW") (pinfunction "RING_SW_RING_SW") (pintype "bidirectional"))
    )
    (net (code "68") (name "unconnected-(JK4-PadTIP_SW)") (class "Default")
      (node (ref "JK4") (pin "TIP_SW") (pinfunction "TIP_SW_TIP_SW") (pintype "bidirectional"))
    )
    (net (code "69") (name "unconnected-(JK5-PadRING_SW)") (class "Default")
      (node (ref "JK5") (pin "RING_SW") (pinfunction "RING_SW_RING_SW") (pintype "bidirectional"))
    )
    (net (code "70") (name "unconnected-(JK5-PadTIP_SW)") (class "Default")
      (node (ref "JK5") (pin "TIP_SW") (pinfunction "TIP_SW_TIP_SW") (pintype "bidirectional"))
    )
    (net (code "71") (name "unconnected-(JK6-PadRING_SW)") (class "Default")
      (node (ref "JK6") (pin "RING_SW") (pinfunction "RING_SW_RING_SW") (pintype "bidirectional"))
    )
    (net (code "72") (name "unconnected-(JK6-PadTIP_SW)") (class "Default")
      (node (ref "JK6") (pin "TIP_SW") (pinfunction "TIP_SW_TIP_SW") (pintype "bidirectional"))
    )
    (net (code "73") (name "unconnected-(JK7-PadRING_SW)") (class "Default")
      (node (ref "JK7") (pin "RING_SW") (pinfunction "RING_SW_RING_SW") (pintype "bidirectional"))
    )
    (net (code "74") (name "unconnected-(JK7-PadTIP_SW)") (class "Default")
      (node (ref "JK7") (pin "TIP_SW") (pinfunction "TIP_SW_TIP_SW") (pintype "bidirectional"))
    )
    (net (code "75") (name "unconnected-(JK8-PadRING_SW)") (class "Default")
      (node (ref "JK8") (pin "RING_SW") (pinfunction "RING_SW_RING_SW") (pintype "bidirectional"))
    )
    (net (code "76") (name "unconnected-(JK8-PadTIP_SW)") (class "Default")
      (node (ref "JK8") (pin "TIP_SW") (pinfunction "TIP_SW_TIP_SW") (pintype "bidirectional"))
    )
    (net (code "77") (name "unconnected-(RV2-E-Pad3)") (class "Default")
      (node (ref "RV2") (pin "3") (pinfunction "E_3") (pintype "passive"))
    )
  )
)
